# A_D_000000_001.net
KiCad netlist of a schematic drawn in Altium Designer
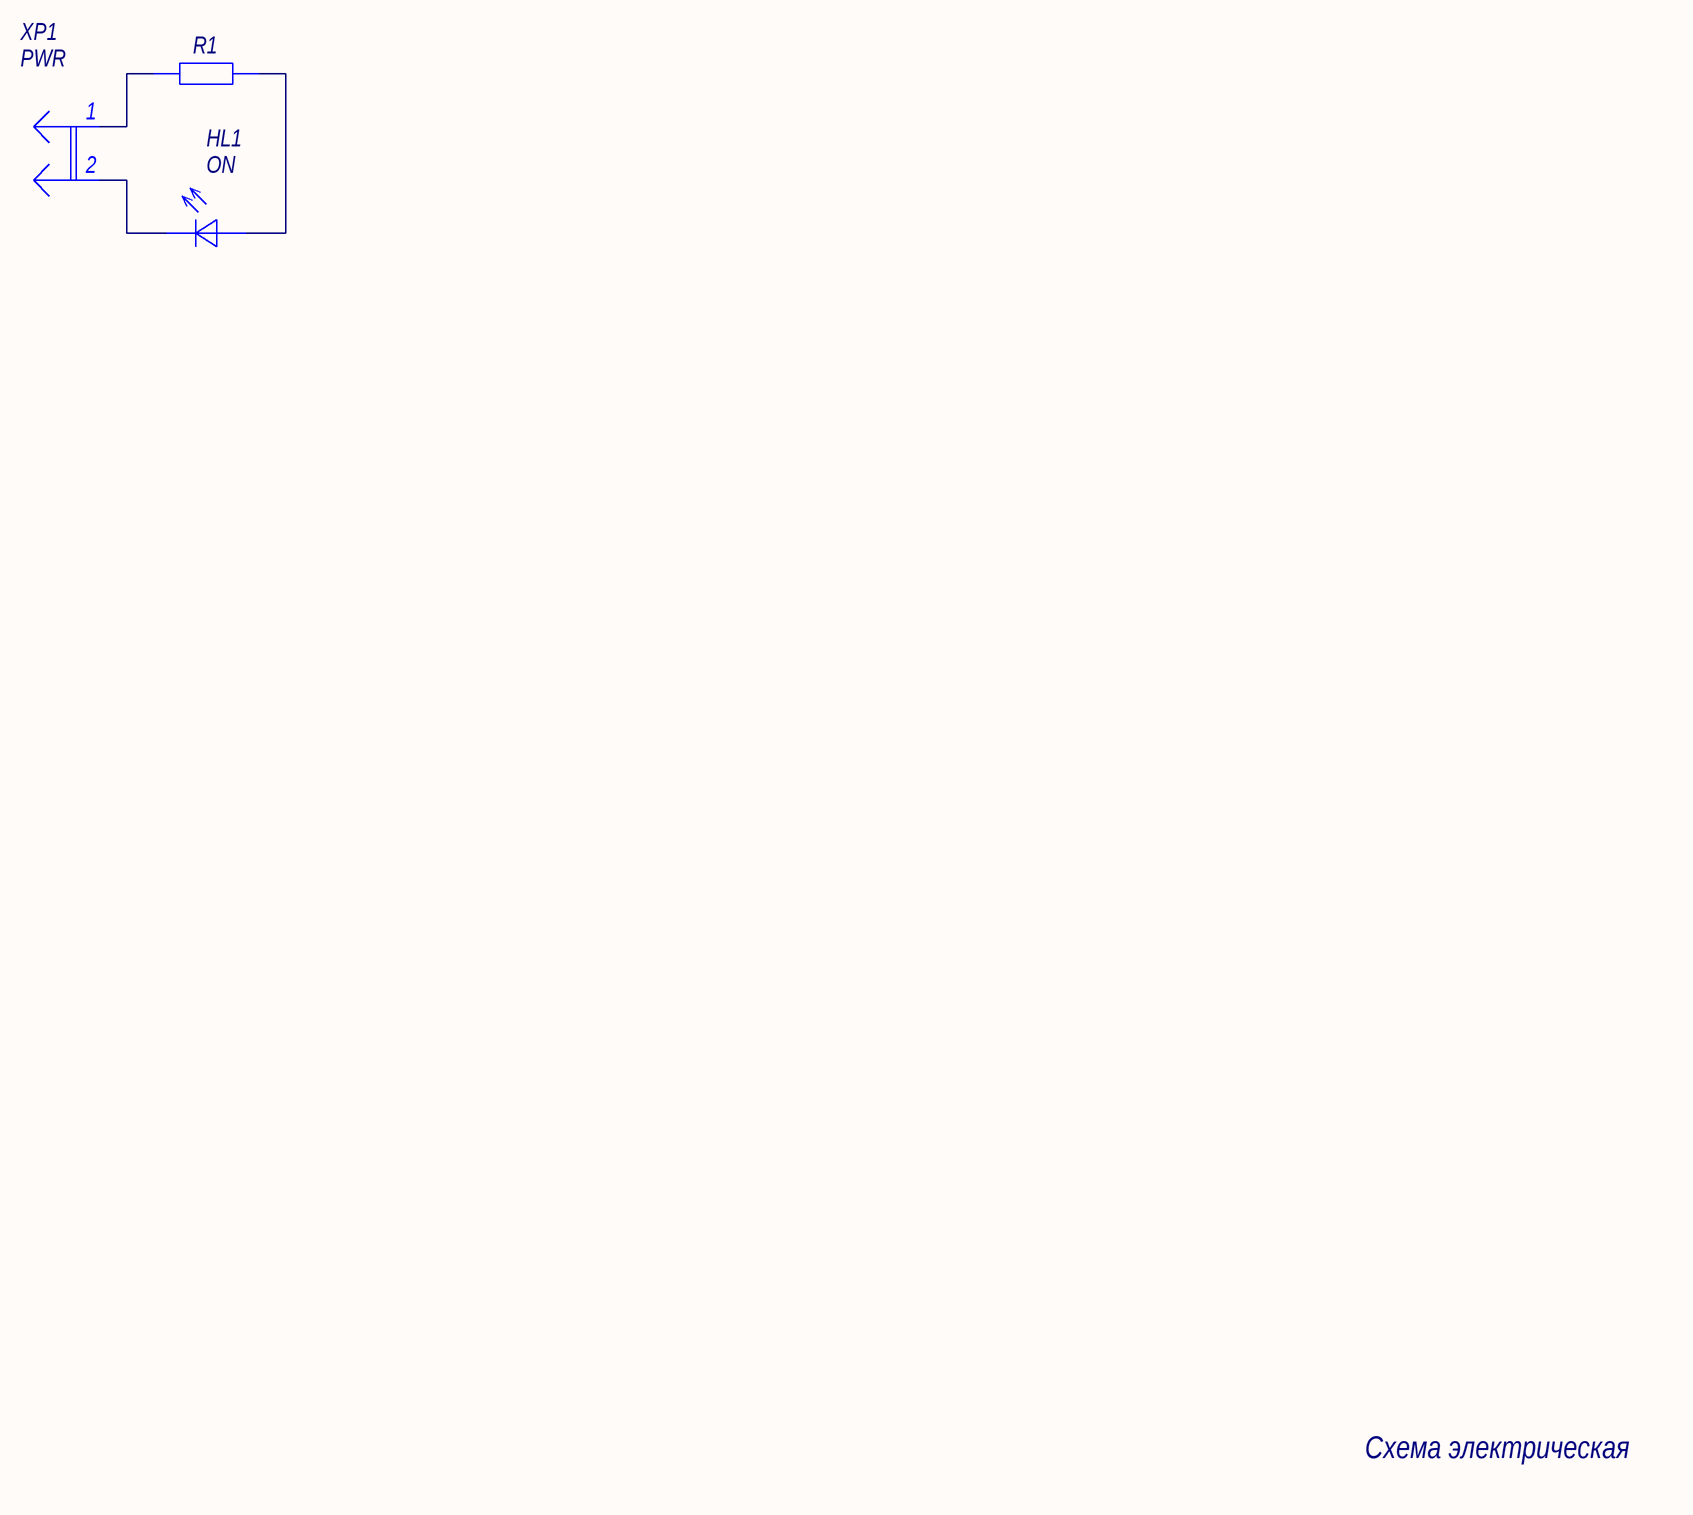
[diagram p0: A_D.000000.001.SchDoc]

(export (version "E")
  (design (tool "Eeschema 10.0.6"))
  (components
    (comp (ref "HL1")
      (value "ON")
      (footprint "LD0603")
      (fields (field (name "PART NUMBER") "BL-LS0603HC") (field (name "PUBLISHER") "Andrew Danich"))
      (libsource (lib "Lib_IMP_GOST") (part "Led-1"))
    )
    (comp (ref "R1")
      (value "Resistor")
      (footprint "R0603")
      (fields
        (field (name "PART NUMBER") "RC0603JR-07330RL")
        (field (name "TOLERANCE") "±5%")
        (field (name "MANUFACTURER") "Yageo")
        (field (name "PUBLISHER") "Andrew Danich")
      )
      (libsource (lib "Lib_IMP_GOST") (part "Resistor"))
    )
    (comp (ref "XP1")
      (value "PWR")
      (footprint "WF-2")
      (fields
        (field (name "PART NUMBER") "WF-2")
        (field (name "MANUFACTURER") "Ningbo Zhenqin Electronic")
        (field (name "PUBLISHER") "Andrew Danich")
      )
      (libsource (lib "Lib_IMP_GOST") (part "Con-2-M"))
    )
  )
  (nets
    (net (code "1") (name "Net-(HL1-А)") (class "Default")
      (node (ref "HL1") (pin "1") (pinfunction "А_1") (pintype "passive"))
      (node (ref "R1") (pin "2") (pinfunction "2_2") (pintype "passive"))
    )
    (net (code "2") (name "Net-(HL1-К)") (class "Default")
      (node (ref "HL1") (pin "2") (pinfunction "К_2") (pintype "passive"))
      (node (ref "XP1") (pin "2") (pintype "passive"))
    )
    (net (code "3") (name "Net-(R1-Pad1)") (class "Default")
      (node (ref "R1") (pin "1") (pinfunction "1_1") (pintype "passive"))
      (node (ref "XP1") (pin "1") (pintype "passive"))
    )
  )
)
